# HW-DC26-Badge-20180426-1_1.net
KiCad netlist of a schematic drawn in EAGLE
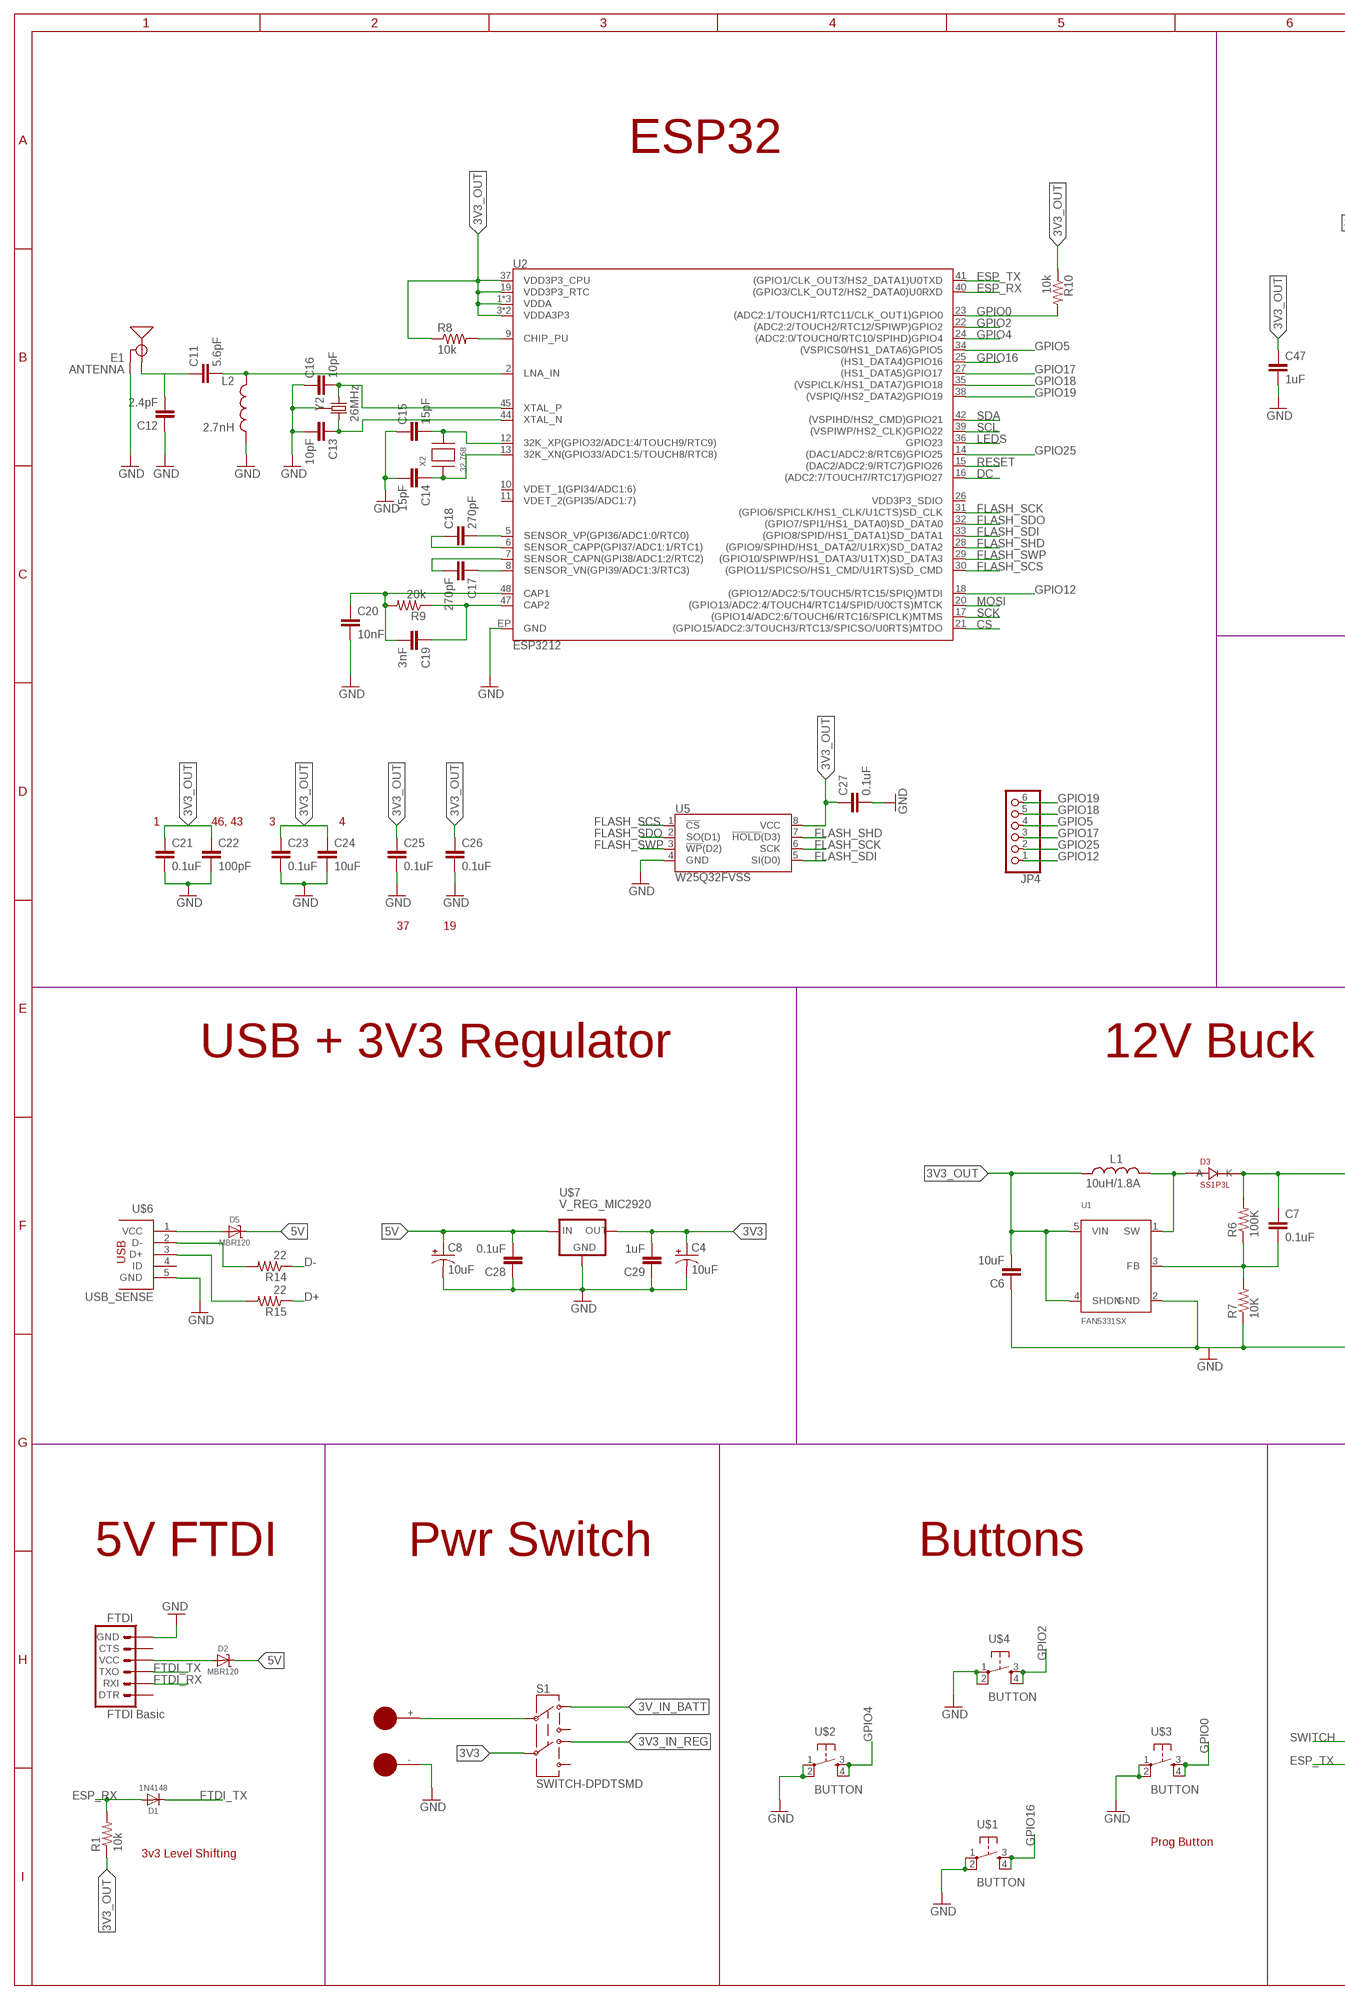
[diagram p0: schematic, sheet 1, part 1 of 2]
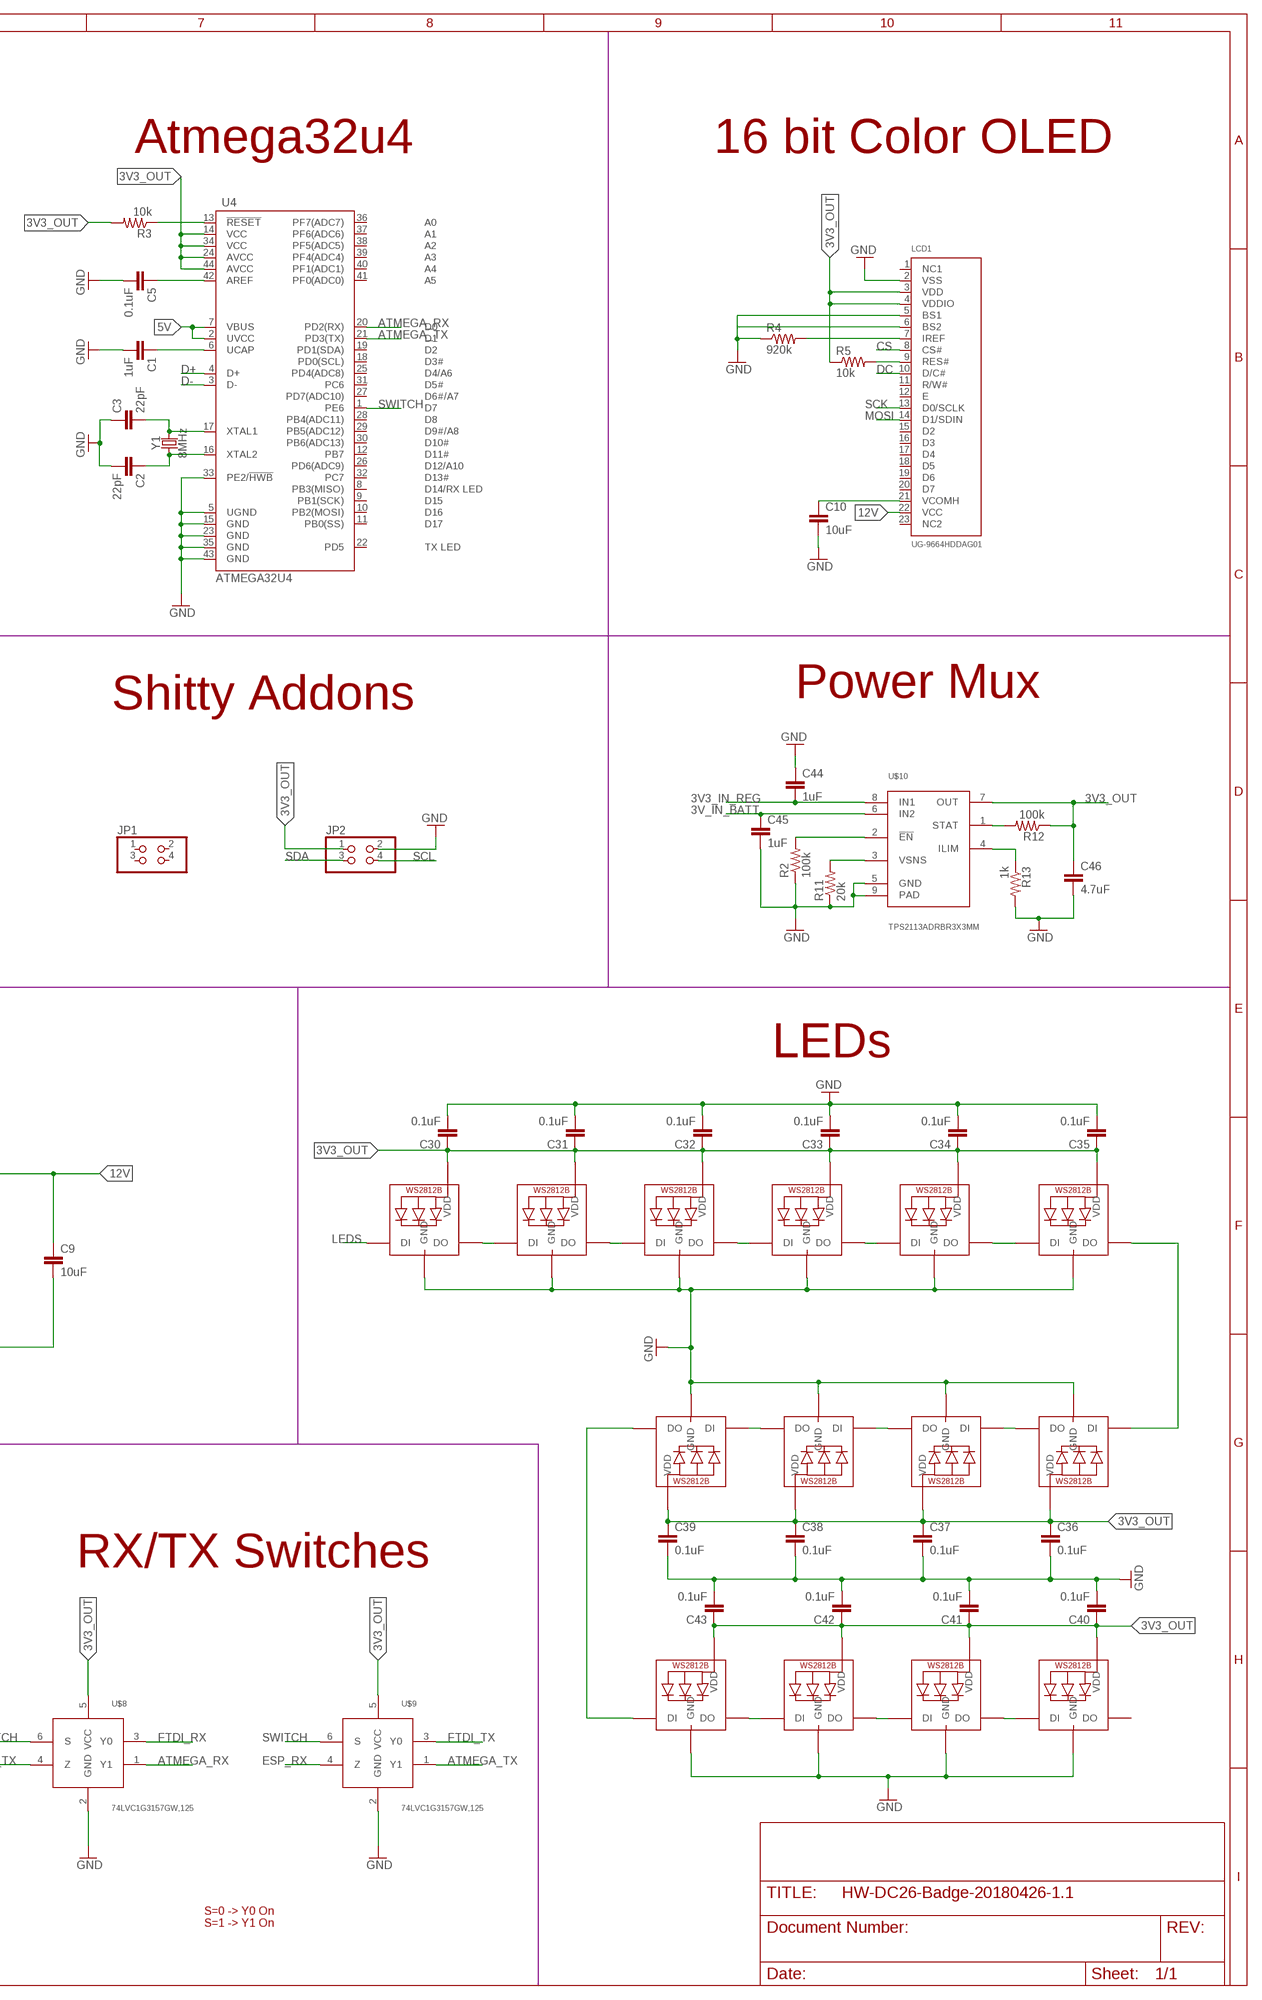
[diagram p1: schematic, sheet 1, part 2 of 2]

(export (version "E")
  (design (tool "Eeschema 10.0.6"))
  (components
    (comp (ref "C1")
      (value "1uF")
      (footprint "eagle-import:CAP0603")
      (libsource (lib "eagle-import") (part "CAP-0603-EMPTY-VALUES"))
    )
    (comp (ref "C2")
      (value "22pF")
      (footprint "eagle-import:CAP0603")
      (libsource (lib "eagle-import") (part "CAP-0603-EMPTY-VALUES"))
    )
    (comp (ref "C3")
      (value "22pF")
      (footprint "eagle-import:CAP0603")
      (libsource (lib "eagle-import") (part "CAP-0603-EMPTY-VALUES"))
    )
    (comp (ref "C4")
      (value "10uF")
      (footprint "eagle-import:EIA3216")
      (libsource (lib "eagle-import") (part "CAP_POL1206"))
    )
    (comp (ref "C5")
      (value "0.1uF")
      (footprint "eagle-import:CAP0603")
      (libsource (lib "eagle-import") (part "CAP-0603-EMPTY-VALUES"))
    )
    (comp (ref "C6")
      (value "10uF")
      (footprint "eagle-import:CAP0603")
      (fields (field (name "TOLERANCE") "10%") (field (name "VOLTAGE") "10V"))
      (libsource (lib "eagle-import") (part "CAP-0603-10UF-10V-10%"))
    )
    (comp (ref "C7")
      (value "0.1uF")
      (footprint "eagle-import:CAP0603")
      (fields (field (name "TOLERANCE") "10%") (field (name "VOLTAGE") "25V"))
      (libsource (lib "eagle-import") (part "CAP-0603-0.1UF-25V-10%"))
    )
    (comp (ref "C8")
      (value "10uF")
      (footprint "eagle-import:EIA3216")
      (libsource (lib "eagle-import") (part "CAP_POL1206"))
    )
    (comp (ref "C9")
      (value "10uF")
      (footprint "eagle-import:CAP0603")
      (fields (field (name "TOLERANCE") "20%") (field (name "VOLTAGE") "25V"))
      (libsource (lib "eagle-import") (part "CAP-0603-10UF-25V-20%"))
    )
    (comp (ref "C10")
      (value "10uF")
      (footprint "eagle-import:CAP0603")
      (libsource (lib "eagle-import") (part "CAP-0603-EMPTY-VALUES"))
    )
    (comp (ref "C11")
      (value "5.6pF")
      (footprint "eagle-import:CAP0603")
      (libsource (lib "eagle-import") (part "CAP-0603-EMPTY-VALUES"))
    )
    (comp (ref "C12")
      (value "2.4pF")
      (footprint "eagle-import:CAP0603")
      (libsource (lib "eagle-import") (part "CAP-0603-EMPTY-VALUES"))
    )
    (comp (ref "C13")
      (value "10pF")
      (footprint "eagle-import:CAP0603")
      (libsource (lib "eagle-import") (part "CAP-0603-EMPTY-VALUES"))
    )
    (comp (ref "C14")
      (value "15pF")
      (footprint "eagle-import:CAP0603")
      (libsource (lib "eagle-import") (part "CAP-0603-EMPTY-VALUES"))
    )
    (comp (ref "C15")
      (value "15pF")
      (footprint "eagle-import:CAP0603")
      (libsource (lib "eagle-import") (part "CAP-0603-EMPTY-VALUES"))
    )
    (comp (ref "C16")
      (value "10pF")
      (footprint "eagle-import:CAP0603")
      (libsource (lib "eagle-import") (part "CAP-0603-EMPTY-VALUES"))
    )
    (comp (ref "C17")
      (value "270pF")
      (footprint "eagle-import:CAP0603")
      (libsource (lib "eagle-import") (part "CAP-0603-EMPTY-VALUES"))
    )
    (comp (ref "C18")
      (value "270pF")
      (footprint "eagle-import:CAP0603")
      (libsource (lib "eagle-import") (part "CAP-0603-EMPTY-VALUES"))
    )
    (comp (ref "C19")
      (value "3nF")
      (footprint "eagle-import:CAP0603")
      (libsource (lib "eagle-import") (part "CAP-0603-EMPTY-VALUES"))
    )
    (comp (ref "C20")
      (value "10nF")
      (footprint "eagle-import:CAP0603")
      (libsource (lib "eagle-import") (part "CAP-0603-EMPTY-VALUES"))
    )
    (comp (ref "C21")
      (value "0.1uF")
      (footprint "eagle-import:CAP0603")
      (libsource (lib "eagle-import") (part "CAP-0603-EMPTY-VALUES"))
    )
    (comp (ref "C22")
      (value "100pF")
      (footprint "eagle-import:CAP0603")
      (libsource (lib "eagle-import") (part "CAP-0603-EMPTY-VALUES"))
    )
    (comp (ref "C23")
      (value "0.1uF")
      (footprint "eagle-import:CAP0603")
      (libsource (lib "eagle-import") (part "CAP-0603-EMPTY-VALUES"))
    )
    (comp (ref "C24")
      (value "10uF")
      (footprint "eagle-import:CAP0603")
      (libsource (lib "eagle-import") (part "CAP-0603-EMPTY-VALUES"))
    )
    (comp (ref "C25")
      (value "0.1uF")
      (footprint "eagle-import:CAP0603")
      (libsource (lib "eagle-import") (part "CAP-0603-EMPTY-VALUES"))
    )
    (comp (ref "C26")
      (value "0.1uF")
      (footprint "eagle-import:CAP0603")
      (libsource (lib "eagle-import") (part "CAP-0603-EMPTY-VALUES"))
    )
    (comp (ref "C27")
      (value "0.1uF")
      (footprint "eagle-import:CAP0603")
      (libsource (lib "eagle-import") (part "CAP-0603-EMPTY-VALUES"))
    )
    (comp (ref "C28")
      (value "0.1uF")
      (footprint "eagle-import:CAP0603")
      (libsource (lib "eagle-import") (part "CAP-0603-EMPTY-VALUES"))
    )
    (comp (ref "C29")
      (value "1uF")
      (footprint "eagle-import:CAP0603")
      (libsource (lib "eagle-import") (part "CAP-0603-EMPTY-VALUES"))
    )
    (comp (ref "C30")
      (value "0.1uF")
      (footprint "eagle-import:CAP0603")
      (libsource (lib "eagle-import") (part "CAP-0603-EMPTY-VALUES"))
    )
    (comp (ref "C31")
      (value "0.1uF")
      (footprint "eagle-import:CAP0603")
      (libsource (lib "eagle-import") (part "CAP-0603-EMPTY-VALUES"))
    )
    (comp (ref "C32")
      (value "0.1uF")
      (footprint "eagle-import:CAP0603")
      (libsource (lib "eagle-import") (part "CAP-0603-EMPTY-VALUES"))
    )
    (comp (ref "C33")
      (value "0.1uF")
      (footprint "eagle-import:CAP0603")
      (libsource (lib "eagle-import") (part "CAP-0603-EMPTY-VALUES"))
    )
    (comp (ref "C34")
      (value "0.1uF")
      (footprint "eagle-import:CAP0603")
      (libsource (lib "eagle-import") (part "CAP-0603-EMPTY-VALUES"))
    )
    (comp (ref "C35")
      (value "0.1uF")
      (footprint "eagle-import:CAP0603")
      (libsource (lib "eagle-import") (part "CAP-0603-EMPTY-VALUES"))
    )
    (comp (ref "C36")
      (value "0.1uF")
      (footprint "eagle-import:CAP0603")
      (libsource (lib "eagle-import") (part "CAP-0603-EMPTY-VALUES"))
    )
    (comp (ref "C37")
      (value "0.1uF")
      (footprint "eagle-import:CAP0603")
      (libsource (lib "eagle-import") (part "CAP-0603-EMPTY-VALUES"))
    )
    (comp (ref "C38")
      (value "0.1uF")
      (footprint "eagle-import:CAP0603")
      (libsource (lib "eagle-import") (part "CAP-0603-EMPTY-VALUES"))
    )
    (comp (ref "C39")
      (value "0.1uF")
      (footprint "eagle-import:CAP0603")
      (libsource (lib "eagle-import") (part "CAP-0603-EMPTY-VALUES"))
    )
    (comp (ref "C40")
      (value "0.1uF")
      (footprint "eagle-import:CAP0603")
      (libsource (lib "eagle-import") (part "CAP-0603-EMPTY-VALUES"))
    )
    (comp (ref "C41")
      (value "0.1uF")
      (footprint "eagle-import:CAP0603")
      (libsource (lib "eagle-import") (part "CAP-0603-EMPTY-VALUES"))
    )
    (comp (ref "C42")
      (value "0.1uF")
      (footprint "eagle-import:CAP0603")
      (libsource (lib "eagle-import") (part "CAP-0603-EMPTY-VALUES"))
    )
    (comp (ref "C43")
      (value "0.1uF")
      (footprint "eagle-import:CAP0603")
      (libsource (lib "eagle-import") (part "CAP-0603-EMPTY-VALUES"))
    )
    (comp (ref "C44")
      (value "1uF")
      (footprint "eagle-import:CAP0603")
      (libsource (lib "eagle-import") (part "CAP-0603-EMPTY-VALUES"))
    )
    (comp (ref "C45")
      (value "1uF")
      (footprint "eagle-import:CAP0603")
      (libsource (lib "eagle-import") (part "CAP-0603-EMPTY-VALUES"))
    )
    (comp (ref "C46")
      (value "4.7uF")
      (footprint "eagle-import:CAP0603")
      (libsource (lib "eagle-import") (part "CAP-0603-EMPTY-VALUES"))
    )
    (comp (ref "C47")
      (value "1uF")
      (footprint "eagle-import:CAP0603")
      (libsource (lib "eagle-import") (part "CAP-0603-EMPTY-VALUES"))
    )
    (comp (ref "D1")
      (value "1N4148")
      (footprint "eagle-import:SOD-323")
      (libsource (lib "eagle-import") (part "DIODESOD-323"))
    )
    (comp (ref "D2")
      (value "MBR120")
      (footprint "eagle-import:SOD-123")
      (libsource (lib "eagle-import") (part "DIODE-SCHOTTKYSOD-123"))
    )
    (comp (ref "D3")
      (value "SS1P3L")
      (footprint "eagle-import:DO220AAL")
      (libsource (lib "eagle-import") (part "SS1P3L"))
    )
    (comp (ref "D5")
      (value "MBR120")
      (footprint "eagle-import:SOD-123")
      (libsource (lib "eagle-import") (part "DIODE-SCHOTTKYSOD-123"))
    )
    (comp (ref "E1")
      (value "ANTENNA")
      (footprint "eagle-import:TRACE_ANTENNA_2.4GHZ_25.7MM_TUNED")
      (libsource (lib "eagle-import") (part "ANTENNATRACE-TUNED"))
    )
    (comp (ref "FTDI")
      (value "FTDI Basic")
      (footprint "eagle-import:1X06")
      (libsource (lib "eagle-import") (part "ARDUINO_SERIAL_PROGRAMPTH"))
    )
    (comp (ref "JP1")
      (value "PINHD-2X2")
      (footprint "eagle-import:2X02")
      (libsource (lib "eagle-import") (part "PINHD-2X2"))
    )
    (comp (ref "JP2")
      (value "PINHD-2X2")
      (footprint "eagle-import:2X02")
      (libsource (lib "eagle-import") (part "PINHD-2X2"))
    )
    (comp (ref "JP4")
      (value "PINHD-1X6")
      (footprint "eagle-import:1X06")
      (libsource (lib "eagle-import") (part "PINHD-1X6"))
    )
    (comp (ref "L1")
      (value "10uH/1.8A")
      (footprint "eagle-import:SRU5028")
      (libsource (lib "eagle-import") (part "INDUCTORSRU5028"))
    )
    (comp (ref "L2")
      (value "2.7nH")
      (footprint "eagle-import:0603")
      (libsource (lib "eagle-import") (part "SparkFun-Passives_INDUCTOR0603"))
    )
    (comp (ref "LCD1")
      (value "UG-9664HDDAG01")
      (footprint "eagle-import:UG-9664HDDAG01_WRAPAROUND")
      (libsource (lib "eagle-import") (part "DISP_OLED_UG-9664HDDAG01WRAPAROUND"))
    )
    (comp (ref "LED1")
      (value "WS2812B3535")
      (footprint "eagle-import:LED3535")
      (libsource (lib "eagle-import") (part "WS2812B3535"))
    )
    (comp (ref "LED2")
      (value "WS2812B3535")
      (footprint "eagle-import:LED3535")
      (libsource (lib "eagle-import") (part "WS2812B3535"))
    )
    (comp (ref "LED3")
      (value "WS2812B3535")
      (footprint "eagle-import:LED3535")
      (libsource (lib "eagle-import") (part "WS2812B3535"))
    )
    (comp (ref "LED4")
      (value "WS2812B3535")
      (footprint "eagle-import:LED3535")
      (libsource (lib "eagle-import") (part "WS2812B3535"))
    )
    (comp (ref "LED5")
      (value "WS2812B3535")
      (footprint "eagle-import:LED3535")
      (libsource (lib "eagle-import") (part "WS2812B3535"))
    )
    (comp (ref "LED6")
      (value "WS2812B3535")
      (footprint "eagle-import:LED3535")
      (libsource (lib "eagle-import") (part "WS2812B3535"))
    )
    (comp (ref "LED7")
      (value "WS2812B3535")
      (footprint "eagle-import:LED3535")
      (libsource (lib "eagle-import") (part "WS2812B3535"))
    )
    (comp (ref "LED8")
      (value "WS2812B3535")
      (footprint "eagle-import:LED3535")
      (libsource (lib "eagle-import") (part "WS2812B3535"))
    )
    (comp (ref "LED9")
      (value "WS2812B3535")
      (footprint "eagle-import:LED3535")
      (libsource (lib "eagle-import") (part "WS2812B3535"))
    )
    (comp (ref "LED10")
      (value "WS2812B3535")
      (footprint "eagle-import:LED3535")
      (libsource (lib "eagle-import") (part "WS2812B3535"))
    )
    (comp (ref "LED11")
      (value "WS2812B3535")
      (footprint "eagle-import:LED3535")
      (libsource (lib "eagle-import") (part "WS2812B3535"))
    )
    (comp (ref "LED12")
      (value "WS2812B3535")
      (footprint "eagle-import:LED3535")
      (libsource (lib "eagle-import") (part "WS2812B3535"))
    )
    (comp (ref "LED13")
      (value "WS2812B3535")
      (footprint "eagle-import:LED3535")
      (libsource (lib "eagle-import") (part "WS2812B3535"))
    )
    (comp (ref "LED14")
      (value "WS2812B3535")
      (footprint "eagle-import:LED3535")
      (libsource (lib "eagle-import") (part "WS2812B3535"))
    )
    (comp (ref "R1")
      (value "10k")
      (footprint "eagle-import:RES-0603")
      (libsource (lib "eagle-import") (part "RES-0603_EMPTY-FIELDS"))
    )
    (comp (ref "R2")
      (value "100k")
      (footprint "eagle-import:RES-0603")
      (libsource (lib "eagle-import") (part "RES-0603_EMPTY-FIELDS"))
    )
    (comp (ref "R3")
      (value "10k")
      (footprint "eagle-import:RES-0603")
      (libsource (lib "eagle-import") (part "RES-0603_EMPTY-FIELDS"))
    )
    (comp (ref "R4")
      (value "920k")
      (footprint "eagle-import:RES-0603")
      (libsource (lib "eagle-import") (part "RES-0603_EMPTY-FIELDS"))
    )
    (comp (ref "R5")
      (value "10k")
      (footprint "eagle-import:RES-0603")
      (libsource (lib "eagle-import") (part "RES-0603_EMPTY-FIELDS"))
    )
    (comp (ref "R6")
      (value "100K")
      (footprint "eagle-import:RES-0603")
      (fields (field (name "TOLERANCE") "5%"))
      (libsource (lib "eagle-import") (part "RES-0603-100K-5%"))
    )
    (comp (ref "R7")
      (value "10K")
      (footprint "eagle-import:RES-0603")
      (fields (field (name "TOLERANCE") "5%"))
      (libsource (lib "eagle-import") (part "RES-0603-10K-5%"))
    )
    (comp (ref "R8")
      (value "10k")
      (footprint "eagle-import:RES-0603")
      (libsource (lib "eagle-import") (part "RES-0603_EMPTY-FIELDS"))
    )
    (comp (ref "R9")
      (value "20k")
      (footprint "eagle-import:RES-0603")
      (libsource (lib "eagle-import") (part "RES-0603_EMPTY-FIELDS"))
    )
    (comp (ref "R10")
      (value "10k")
      (footprint "eagle-import:RES-0603")
      (libsource (lib "eagle-import") (part "RES-0603_EMPTY-FIELDS"))
    )
    (comp (ref "R11")
      (value "20k")
      (footprint "eagle-import:RES-0603")
      (libsource (lib "eagle-import") (part "RES-0603_EMPTY-FIELDS"))
    )
    (comp (ref "R12")
      (value "100k")
      (footprint "eagle-import:RES-0603")
      (libsource (lib "eagle-import") (part "RES-0603_EMPTY-FIELDS"))
    )
    (comp (ref "R13")
      (value "1k")
      (footprint "eagle-import:RES-0603")
      (libsource (lib "eagle-import") (part "RES-0603_EMPTY-FIELDS"))
    )
    (comp (ref "R14")
      (value "22")
      (footprint "eagle-import:RES-0603")
      (libsource (lib "eagle-import") (part "RES-0603_EMPTY-FIELDS"))
    )
    (comp (ref "R15")
      (value "22")
      (footprint "eagle-import:RES-0603")
      (libsource (lib "eagle-import") (part "RES-0603_EMPTY-FIELDS"))
    )
    (comp (ref "S1")
      (value "SWITCH-DPDTSMD")
      (footprint "eagle-import:AYZ0202")
      (libsource (lib "eagle-import") (part "SWITCH-DPDTSMD"))
    )
    (comp (ref "U$1")
      (value "BUTTON")
      (footprint "eagle-import:BUTTON")
      (libsource (lib "eagle-import") (part "BUTTON"))
    )
    (comp (ref "U$2")
      (value "BUTTON")
      (footprint "eagle-import:BUTTON")
      (libsource (lib "eagle-import") (part "BUTTON"))
    )
    (comp (ref "U$3")
      (value "BUTTON")
      (footprint "eagle-import:BUTTON")
      (libsource (lib "eagle-import") (part "BUTTON"))
    )
    (comp (ref "U$4")
      (value "BUTTON")
      (footprint "eagle-import:BUTTON")
      (libsource (lib "eagle-import") (part "BUTTON"))
    )
    (comp (ref "U$5")
      (value "BAT_HOLD")
      (footprint "eagle-import:AA")
      (libsource (lib "eagle-import") (part "BAT_HOLD"))
    )
    (comp (ref "U$6")
      (value "USB_SENSE")
      (footprint "eagle-import:USB-MICRO-TH-SUPPORT")
      (libsource (lib "eagle-import") (part "USB_SENSE"))
    )
    (comp (ref "U$7")
      (value "V_REG_MIC2920")
      (footprint "eagle-import:SOT223")
      (libsource (lib "eagle-import") (part "V_REG_MIC2920"))
    )
    (comp (ref "U$8")
      (value "74LVC1G3157GW,125")
      (footprint "eagle-import:SOT-363")
      (libsource (lib "eagle-import") (part "74LVC1G3157GW,125"))
    )
    (comp (ref "U$9")
      (value "74LVC1G3157GW,125")
      (footprint "eagle-import:SOT-363")
      (libsource (lib "eagle-import") (part "74LVC1G3157GW,125"))
    )
    (comp (ref "U$10")
      (value "TPS2113ADRBR3X3MM")
      (footprint "eagle-import:8-VDFN")
      (libsource (lib "eagle-import") (part "TPS2113ADRBR3X3MM"))
    )
    (comp (ref "U1")
      (value "FAN5331SX")
      (footprint "eagle-import:SOT23-5")
      (libsource (lib "eagle-import") (part "FAN5331"))
    )
    (comp (ref "U2")
      (value "ESP3212")
      (footprint "eagle-import:QFN48-0.4MM")
      (libsource (lib "eagle-import") (part "ESP3212"))
    )
    (comp (ref "U4")
      (value "ATMEGA32U4")
      (footprint "eagle-import:QFN-44-NOPAD_1_1-OUTFAKES")
      (libsource (lib "eagle-import") (part "ATMEGA32U4OUTFAKES"))
    )
    (comp (ref "U5")
      (value "W25Q32FVSS")
      (footprint "eagle-import:SOIC-8")
      (libsource (lib "eagle-import") (part "W25Q32FVSS"))
    )
    (comp (ref "X2")
      (value "32.768")
      (footprint "eagle-import:XTAL3215")
      (libsource (lib "eagle-import") (part "XTAL-3.2X1.5"))
    )
    (comp (ref "Y1")
      (value "8MHz")
      (footprint "eagle-import:CRYSTAL-SMD-5X3.2-4PAD")
      (libsource (lib "eagle-import") (part "CRYSTAL-8MHZSMD-5X3.2"))
    )
    (comp (ref "Y2")
      (value "26MHz")
      (footprint "eagle-import:CRYSTAL-SMD-3.2X2.5")
      (libsource (lib "eagle-import") (part "CRYSTAL-GROUNDED3.2X2.5"))
    )
  )
  (nets
    (net (code "1") (name "/ATMEGA_RX") (class "Default")
      (node (ref "U$8") (pin "1") (pinfunction "Y1_1") (pintype "bidirectional"))
      (node (ref "U4") (pin "20") (pinfunction "PD2(RX)_20") (pintype "bidirectional"))
    )
    (net (code "2") (name "/ATMEGA_TX") (class "Default")
      (node (ref "U$9") (pin "1") (pinfunction "Y1_1") (pintype "bidirectional"))
      (node (ref "U4") (pin "21") (pinfunction "PD3(TX)_21") (pintype "bidirectional"))
    )
    (net (code "3") (name "/CS") (class "Default")
      (node (ref "LCD1") (pin "8") (pinfunction "CS#_8") (pintype "bidirectional"))
      (node (ref "U2") (pin "21") (pinfunction "(GPIO15/ADC2:3/TOUCH3/RTC13/SPICSO/U0RTS)MTDO_21") (pintype "bidirectional"))
    )
    (net (code "4") (name "/D+") (class "Default")
      (node (ref "R15") (pin "1") (pinfunction "1_1") (pintype "passive"))
      (node (ref "U4") (pin "4") (pinfunction "D+_4") (pintype "bidirectional"))
    )
    (net (code "5") (name "/D-") (class "Default")
      (node (ref "R14") (pin "1") (pinfunction "1_1") (pintype "passive"))
      (node (ref "U4") (pin "3") (pinfunction "D-_3") (pintype "bidirectional"))
    )
    (net (code "6") (name "/DC") (class "Default")
      (node (ref "LCD1") (pin "10") (pinfunction "D/C#_10") (pintype "bidirectional"))
      (node (ref "U2") (pin "16") (pinfunction "(ADC2:7/TOUCH7/RTC17)GPIO27_16") (pintype "bidirectional"))
    )
    (net (code "7") (name "/ESP_RX") (class "Default")
      (node (ref "D1") (pin "A") (pinfunction "A_A") (pintype "passive"))
      (node (ref "R1") (pin "2") (pinfunction "2_2") (pintype "passive"))
      (node (ref "U$9") (pin "4") (pinfunction "Z_4") (pintype "bidirectional"))
      (node (ref "U2") (pin "40") (pinfunction "(GPIO3/CLK_OUT2/HS2_DATA0)U0RXD_40") (pintype "bidirectional"))
    )
    (net (code "8") (name "/ESP_TX") (class "Default")
      (node (ref "U$8") (pin "4") (pinfunction "Z_4") (pintype "bidirectional"))
      (node (ref "U2") (pin "41") (pinfunction "(GPIO1/CLK_OUT3/HS2_DATA1)U0TXD_41") (pintype "bidirectional"))
    )
    (net (code "9") (name "/FLASH_SCK") (class "Default")
      (node (ref "U2") (pin "31") (pinfunction "(GPIO6/SPICLK/HS1_CLK/U1CTS)SD_CLK_31") (pintype "bidirectional"))
      (node (ref "U5") (pin "6") (pinfunction "SCK_6") (pintype "bidirectional"))
    )
    (net (code "10") (name "/FLASH_SCS") (class "Default")
      (node (ref "U2") (pin "30") (pinfunction "(GPIO11/SPICSO/HS1_CMD/U1RTS)SD_CMD_30") (pintype "bidirectional"))
      (node (ref "U5") (pin "1") (pinfunction "~{CS}_1") (pintype "bidirectional"))
    )
    (net (code "11") (name "/FLASH_SDI") (class "Default")
      (node (ref "U2") (pin "33") (pinfunction "(GPIO8/SPID/HS1_DATA1)SD_DATA1_33") (pintype "bidirectional"))
      (node (ref "U5") (pin "5") (pinfunction "SI(D0)_5") (pintype "bidirectional"))
    )
    (net (code "12") (name "/FLASH_SDO") (class "Default")
      (node (ref "U2") (pin "32") (pinfunction "(GPIO7/SPI1/HS1_DATA0)SD_DATA0_32") (pintype "bidirectional"))
      (node (ref "U5") (pin "2") (pinfunction "SO(D1)_2") (pintype "bidirectional"))
    )
    (net (code "13") (name "/FLASH_SHD") (class "Default")
      (node (ref "U2") (pin "28") (pinfunction "(GPIO9/SPIHD/HS1_DATA2/U1RX)SD_DATA2_28") (pintype "bidirectional"))
      (node (ref "U5") (pin "7") (pinfunction "~{HOLD}(D3)_7") (pintype "bidirectional"))
    )
    (net (code "14") (name "/FLASH_SWP") (class "Default")
      (node (ref "U2") (pin "29") (pinfunction "(GPIO10/SPIWP/HS1_DATA3/U1TX)SD_DATA3_29") (pintype "bidirectional"))
      (node (ref "U5") (pin "3") (pinfunction "~{WP}(D2)_3") (pintype "bidirectional"))
    )
    (net (code "15") (name "/FTDI_RX") (class "Default")
      (node (ref "FTDI") (pin "2") (pinfunction "RXI_2") (pintype "passive"))
      (node (ref "U$8") (pin "3") (pinfunction "Y0_3") (pintype "bidirectional"))
    )
    (net (code "16") (name "/FTDI_TX") (class "Default")
      (node (ref "D1") (pin "C") (pinfunction "C_C") (pintype "passive"))
      (node (ref "FTDI") (pin "3") (pinfunction "TXO_3") (pintype "passive"))
      (node (ref "U$9") (pin "3") (pinfunction "Y0_3") (pintype "bidirectional"))
    )
    (net (code "17") (name "/GPIO0") (class "Default")
      (node (ref "R10") (pin "2") (pinfunction "2_2") (pintype "passive"))
      (node (ref "U$3") (pin "3") (pinfunction "3_3") (pintype "passive"))
      (node (ref "U$3") (pin "4") (pinfunction "4_4") (pintype "passive"))
      (node (ref "U2") (pin "23") (pinfunction "(ADC2:1/TOUCH1/RTC11/CLK_OUT1)GPIO0_23") (pintype "bidirectional"))
    )
    (net (code "18") (name "/GPIO2") (class "Default")
      (node (ref "U$4") (pin "3") (pinfunction "3_3") (pintype "passive"))
      (node (ref "U$4") (pin "4") (pinfunction "4_4") (pintype "passive"))
      (node (ref "U2") (pin "22") (pinfunction "(ADC2:2/TOUCH2/RTC12/SPIWP)GPIO2_22") (pintype "bidirectional"))
    )
    (net (code "19") (name "/GPIO4") (class "Default")
      (node (ref "U$2") (pin "3") (pinfunction "3_3") (pintype "passive"))
      (node (ref "U$2") (pin "4") (pinfunction "4_4") (pintype "passive"))
      (node (ref "U2") (pin "24") (pinfunction "(ADC2:0/TOUCH0/RTC10/SPIHD)GPIO4_24") (pintype "bidirectional"))
    )
    (net (code "20") (name "/GPIO5") (class "Default")
      (node (ref "JP4") (pin "4") (pinfunction "4_4") (pintype "passive"))
      (node (ref "U2") (pin "34") (pinfunction "(VSPICS0/HS1_DATA6)GPIO5_34") (pintype "bidirectional"))
    )
    (net (code "21") (name "/GPIO12") (class "Default")
      (node (ref "JP4") (pin "1") (pinfunction "1_1") (pintype "passive"))
      (node (ref "U2") (pin "18") (pinfunction "(GPIO12/ADC2:5/TOUCH5/RTC15/SPIQ)MTDI_18") (pintype "bidirectional"))
    )
    (net (code "22") (name "/GPIO16") (class "Default")
      (node (ref "U$1") (pin "3") (pinfunction "3_3") (pintype "passive"))
      (node (ref "U$1") (pin "4") (pinfunction "4_4") (pintype "passive"))
      (node (ref "U2") (pin "25") (pinfunction "(HS1_DATA4)GPIO16_25") (pintype "bidirectional"))
    )
    (net (code "23") (name "/GPIO17") (class "Default")
      (node (ref "JP4") (pin "3") (pinfunction "3_3") (pintype "passive"))
      (node (ref "U2") (pin "27") (pinfunction "(HS1_DATA5)GPIO17_27") (pintype "bidirectional"))
    )
    (net (code "24") (name "/GPIO18") (class "Default")
      (node (ref "JP4") (pin "5") (pinfunction "5_5") (pintype "passive"))
      (node (ref "U2") (pin "35") (pinfunction "(VSPICLK/HS1_DATA7)GPIO18_35") (pintype "bidirectional"))
    )
    (net (code "25") (name "/GPIO19") (class "Default")
      (node (ref "JP4") (pin "6") (pinfunction "6_6") (pintype "passive"))
      (node (ref "U2") (pin "38") (pinfunction "(VSPIQ/HS2_DATA2)GPIO19_38") (pintype "bidirectional"))
    )
    (net (code "26") (name "/GPIO25") (class "Default")
      (node (ref "JP4") (pin "2") (pinfunction "2_2") (pintype "passive"))
      (node (ref "U2") (pin "14") (pinfunction "(DAC1/ADC2:8/RTC6)GPIO25_14") (pintype "bidirectional"))
    )
    (net (code "27") (name "/LEDS") (class "Default")
      (node (ref "LED5") (pin "1") (pinfunction "DI_1") (pintype "input"))
      (node (ref "U2") (pin "36") (pinfunction "GPIO23_36") (pintype "bidirectional"))
    )
    (net (code "28") (name "/MOSI") (class "Default")
      (node (ref "LCD1") (pin "14") (pinfunction "D1/SDIN_14") (pintype "bidirectional"))
      (node (ref "U2") (pin "20") (pinfunction "(GPIO13/ADC2:4/TOUCH4/RTC14/SPID/U0CTS)MTCK_20") (pintype "bidirectional"))
    )
    (net (code "29") (name "/RESET") (class "Default")
      (node (ref "LCD1") (pin "9") (pinfunction "RES#_9") (pintype "bidirectional"))
      (node (ref "R5") (pin "2") (pinfunction "2_2") (pintype "passive"))
      (node (ref "U2") (pin "15") (pinfunction "(DAC2/ADC2:9/RTC7)GPIO26_15") (pintype "bidirectional"))
    )
    (net (code "30") (name "/SCK") (class "Default")
      (node (ref "LCD1") (pin "13") (pinfunction "D0/SCLK_13") (pintype "bidirectional"))
      (node (ref "U2") (pin "17") (pinfunction "(GPIO14/ADC2:6/TOUCH6/RTC16/SPICLK)MTMS_17") (pintype "bidirectional"))
    )
    (net (code "31") (name "/SCL") (class "Default")
      (node (ref "JP2") (pin "4") (pinfunction "4_4") (pintype "passive"))
      (node (ref "U2") (pin "39") (pinfunction "(VSPIWP/HS2_CLK)GPIO22_39") (pintype "bidirectional"))
    )
    (net (code "32") (name "/SDA") (class "Default")
      (node (ref "JP2") (pin "3") (pinfunction "3_3") (pintype "passive"))
      (node (ref "U2") (pin "42") (pinfunction "(VSPIHD/HS2_CMD)GPIO21_42") (pintype "bidirectional"))
    )
    (net (code "33") (name "/SWITCH") (class "Default")
      (node (ref "U$8") (pin "6") (pinfunction "S_6") (pintype "bidirectional"))
      (node (ref "U$9") (pin "6") (pinfunction "S_6") (pintype "bidirectional"))
      (node (ref "U4") (pin "1") (pinfunction "PE6_1") (pintype "bidirectional"))
    )
    (net (code "34") (name "3V3") (class "Default")
      (node (ref "C29") (pin "2") (pinfunction "2_2") (pintype "passive"))
      (node (ref "C4") (pin "A") (pinfunction "+_A") (pintype "passive"))
      (node (ref "S1") (pin "5") (pinfunction "5_5") (pintype "bidirectional"))
      (node (ref "U$7") (pin "3") (pinfunction "OUT_3") (pintype "output"))
    )
    (net (code "35") (name "3V3_IN_REG") (class "Default")
      (node (ref "C44") (pin "2") (pinfunction "2_2") (pintype "passive"))
      (node (ref "S1") (pin "4") (pinfunction "4_4") (pintype "bidirectional"))
      (node (ref "U$10") (pin "8") (pinfunction "IN1_8") (pintype "bidirectional"))
    )
    (net (code "36") (name "3V3_OUT") (class "Default")
      (node (ref "C21") (pin "1") (pinfunction "1_1") (pintype "passive"))
      (node (ref "C22") (pin "1") (pinfunction "1_1") (pintype "passive"))
      (node (ref "C23") (pin "1") (pinfunction "1_1") (pintype "passive"))
      (node (ref "C24") (pin "1") (pinfunction "1_1") (pintype "passive"))
      (node (ref "C25") (pin "1") (pinfunction "1_1") (pintype "passive"))
      (node (ref "C26") (pin "1") (pinfunction "1_1") (pintype "passive"))
      (node (ref "C27") (pin "1") (pinfunction "1_1") (pintype "passive"))
      (node (ref "C30") (pin "1") (pinfunction "1_1") (pintype "passive"))
      (node (ref "C31") (pin "1") (pinfunction "1_1") (pintype "passive"))
      (node (ref "C32") (pin "1") (pinfunction "1_1") (pintype "passive"))
      (node (ref "C33") (pin "1") (pinfunction "1_1") (pintype "passive"))
      (node (ref "C34") (pin "1") (pinfunction "1_1") (pintype "passive"))
      (node (ref "C35") (pin "1") (pinfunction "1_1") (pintype "passive"))
      (node (ref "C36") (pin "1") (pinfunction "1_1") (pintype "passive"))
      (node (ref "C37") (pin "1") (pinfunction "1_1") (pintype "passive"))
      (node (ref "C38") (pin "1") (pinfunction "1_1") (pintype "passive"))
      (node (ref "C39") (pin "1") (pinfunction "1_1") (pintype "passive"))
      (node (ref "C40") (pin "1") (pinfunction "1_1") (pintype "passive"))
      (node (ref "C41") (pin "1") (pinfunction "1_1") (pintype "passive"))
      (node (ref "C42") (pin "1") (pinfunction "1_1") (pintype "passive"))
      (node (ref "C43") (pin "1") (pinfunction "1_1") (pintype "passive"))
      (node (ref "C46") (pin "1") (pinfunction "1_1") (pintype "passive"))
      (node (ref "C47") (pin "1") (pinfunction "1_1") (pintype "passive"))
      (node (ref "C6") (pin "2") (pinfunction "2_2") (pintype "passive"))
      (node (ref "JP2") (pin "1") (pinfunction "1_1") (pintype "passive"))
      (node (ref "L1") (pin "1") (pinfunction "1_1") (pintype "passive"))
      (node (ref "LCD1") (pin "3") (pinfunction "VDD_3") (pintype "bidirectional"))
      (node (ref "LCD1") (pin "4") (pinfunction "VDDIO_4") (pintype "bidirectional"))
      (node (ref "LED1") (pin "2") (pinfunction "VDD_2") (pintype "power_in"))
      (node (ref "LED10") (pin "2") (pinfunction "VDD_2") (pintype "power_in"))
      (node (ref "LED11") (pin "2") (pinfunction "VDD_2") (pintype "power_in"))
      (node (ref "LED12") (pin "2") (pinfunction "VDD_2") (pintype "power_in"))
      (node (ref "LED13") (pin "2") (pinfunction "VDD_2") (pintype "power_in"))
      (node (ref "LED14") (pin "2") (pinfunction "VDD_2") (pintype "power_in"))
      (node (ref "LED2") (pin "2") (pinfunction "VDD_2") (pintype "power_in"))
      (node (ref "LED3") (pin "2") (pinfunction "VDD_2") (pintype "power_in"))
      (node (ref "LED4") (pin "2") (pinfunction "VDD_2") (pintype "power_in"))
      (node (ref "LED5") (pin "2") (pinfunction "VDD_2") (pintype "power_in"))
      (node (ref "LED6") (pin "2") (pinfunction "VDD_2") (pintype "power_in"))
      (node (ref "LED7") (pin "2") (pinfunction "VDD_2") (pintype "power_in"))
      (node (ref "LED8") (pin "2") (pinfunction "VDD_2") (pintype "power_in"))
      (node (ref "LED9") (pin "2") (pinfunction "VDD_2") (pintype "power_in"))
      (node (ref "R1") (pin "1") (pinfunction "1_1") (pintype "passive"))
      (node (ref "R10") (pin "1") (pinfunction "1_1") (pintype "passive"))
      (node (ref "R12") (pin "1") (pinfunction "1_1") (pintype "passive"))
      (node (ref "R3") (pin "2") (pinfunction "2_2") (pintype "passive"))
      (node (ref "R5") (pin "1") (pinfunction "1_1") (pintype "passive"))
      (node (ref "R8") (pin "1") (pinfunction "1_1") (pintype "passive"))
      (node (ref "U$10") (pin "7") (pinfunction "OUT_7") (pintype "bidirectional"))
      (node (ref "U$8") (pin "5") (pinfunction "VCC_5") (pintype "bidirectional"))
      (node (ref "U$9") (pin "5") (pinfunction "VCC_5") (pintype "bidirectional"))
      (node (ref "U1") (pin "4") (pinfunction "SHDN_4") (pintype "bidirectional"))
      (node (ref "U1") (pin "5") (pinfunction "VIN_5") (pintype "bidirectional"))
      (node (ref "U2") (pin "1") (pinfunction "VDDA_1") (pintype "bidirectional"))
      (node (ref "U2") (pin "19") (pinfunction "VDD3P3_RTC_19") (pintype "bidirectional"))
      (node (ref "U2") (pin "3") (pinfunction "VDDA3P3_3") (pintype "bidirectional"))
      (node (ref "U2") (pin "37") (pinfunction "VDD3P3_CPU_37") (pintype "bidirectional"))
      (node (ref "U2") (pin "4") (pinfunction "VDDA3P3_4") (pintype "bidirectional"))
      (node (ref "U2") (pin "43") (pinfunction "VDDA_43") (pintype "bidirectional"))
      (node (ref "U2") (pin "46") (pinfunction "VDDA_46") (pintype "bidirectional"))
      (node (ref "U4") (pin "14") (pinfunction "VCC_14") (pintype "bidirectional"))
      (node (ref "U4") (pin "24") (pinfunction "AVCC_24") (pintype "bidirectional"))
      (node (ref "U4") (pin "34") (pinfunction "VCC_34") (pintype "bidirectional"))
      (node (ref "U4") (pin "44") (pinfunction "AVCC_44") (pintype "bidirectional"))
      (node (ref "U5") (pin "8") (pinfunction "VCC_8") (pintype "bidirectional"))
    )
    (net (code "37") (name "3V_IN_BATT") (class "Default")
      (node (ref "C45") (pin "1") (pinfunction "1_1") (pintype "passive"))
      (node (ref "S1") (pin "1") (pinfunction "1_1") (pintype "bidirectional"))
      (node (ref "U$10") (pin "6") (pinfunction "IN2_6") (pintype "bidirectional"))
    )
    (net (code "38") (name "5V") (class "Default")
      (node (ref "C28") (pin "2") (pinfunction "2_2") (pintype "passive"))
      (node (ref "C8") (pin "A") (pinfunction "+_A") (pintype "passive"))
      (node (ref "D2") (pin "C") (pinfunction "C_C") (pintype "passive"))
      (node (ref "D5") (pin "C") (pinfunction "C_C") (pintype "passive"))
      (node (ref "U$7") (pin "1") (pinfunction "IN_1") (pintype "input"))
      (node (ref "U4") (pin "2") (pinfunction "UVCC_2") (pintype "bidirectional"))
      (node (ref "U4") (pin "7") (pinfunction "VBUS_7") (pintype "bidirectional"))
    )
    (net (code "39") (name "12V") (class "Default")
      (node (ref "C7") (pin "1") (pinfunction "1_1") (pintype "passive"))
      (node (ref "C9") (pin "1") (pinfunction "1_1") (pintype "passive"))
      (node (ref "D3") (pin "P$1") (pinfunction "K_P$1") (pintype "bidirectional"))
      (node (ref "LCD1") (pin "22") (pinfunction "VCC_22") (pintype "bidirectional"))
      (node (ref "R6") (pin "2") (pinfunction "2_2") (pintype "passive"))
    )
    (net (code "40") (name "GND") (class "Default")
      (node (ref "C1") (pin "2") (pinfunction "2_2") (pintype "passive"))
      (node (ref "C10") (pin "2") (pinfunction "2_2") (pintype "passive"))
      (node (ref "C12") (pin "1") (pinfunction "1_1") (pintype "passive"))
      (node (ref "C13") (pin "2") (pinfunction "2_2") (pintype "passive"))
      (node (ref "C14") (pin "2") (pinfunction "2_2") (pintype "passive"))
      (node (ref "C15") (pin "1") (pinfunction "1_1") (pintype "passive"))
      (node (ref "C16") (pin "1") (pinfunction "1_1") (pintype "passive"))
      (node (ref "C2") (pin "2") (pinfunction "2_2") (pintype "passive"))
      (node (ref "C20") (pin "2") (pinfunction "2_2") (pintype "passive"))
      (node (ref "C21") (pin "2") (pinfunction "2_2") (pintype "passive"))
      (node (ref "C22") (pin "2") (pinfunction "2_2") (pintype "passive"))
      (node (ref "C23") (pin "2") (pinfunction "2_2") (pintype "passive"))
      (node (ref "C24") (pin "2") (pinfunction "2_2") (pintype "passive"))
      (node (ref "C25") (pin "2") (pinfunction "2_2") (pintype "passive"))
      (node (ref "C26") (pin "2") (pinfunction "2_2") (pintype "passive"))
      (node (ref "C27") (pin "2") (pinfunction "2_2") (pintype "passive"))
      (node (ref "C28") (pin "1") (pinfunction "1_1") (pintype "passive"))
      (node (ref "C29") (pin "1") (pinfunction "1_1") (pintype "passive"))
      (node (ref "C3") (pin "1") (pinfunction "1_1") (pintype "passive"))
      (node (ref "C30") (pin "2") (pinfunction "2_2") (pintype "passive"))
      (node (ref "C31") (pin "2") (pinfunction "2_2") (pintype "passive"))
      (node (ref "C32") (pin "2") (pinfunction "2_2") (pintype "passive"))
      (node (ref "C33") (pin "2") (pinfunction "2_2") (pintype "passive"))
      (node (ref "C34") (pin "2") (pinfunction "2_2") (pintype "passive"))
      (node (ref "C35") (pin "2") (pinfunction "2_2") (pintype "passive"))
      (node (ref "C36") (pin "2") (pinfunction "2_2") (pintype "passive"))
      (node (ref "C37") (pin "2") (pinfunction "2_2") (pintype "passive"))
      (node (ref "C38") (pin "2") (pinfunction "2_2") (pintype "passive"))
      (node (ref "C39") (pin "2") (pinfunction "2_2") (pintype "passive"))
      (node (ref "C4") (pin "C") (pinfunction "-_C") (pintype "passive"))
      (node (ref "C40") (pin "2") (pinfunction "2_2") (pintype "passive"))
      (node (ref "C41") (pin "2") (pinfunction "2_2") (pintype "passive"))
      (node (ref "C42") (pin "2") (pinfunction "2_2") (pintype "passive"))
      (node (ref "C43") (pin "2") (pinfunction "2_2") (pintype "passive"))
      (node (ref "C44") (pin "1") (pinfunction "1_1") (pintype "passive"))
      (node (ref "C45") (pin "2") (pinfunction "2_2") (pintype "passive"))
      (node (ref "C46") (pin "2") (pinfunction "2_2") (pintype "passive"))
      (node (ref "C47") (pin "2") (pinfunction "2_2") (pintype "passive"))
      (node (ref "C5") (pin "2") (pinfunction "2_2") (pintype "passive"))
      (node (ref "C6") (pin "1") (pinfunction "1_1") (pintype "passive"))
      (node (ref "C8") (pin "C") (pinfunction "-_C") (pintype "passive"))
      (node (ref "C9") (pin "2") (pinfunction "2_2") (pintype "passive"))
      (node (ref "E1") (pin "GND") (pinfunction "GND_GND") (pintype "bidirectional"))
      (node (ref "E1") (pin "GND2") (pinfunction "GND_GND2") (pintype "bidirectional"))
      (node (ref "FTDI") (pin "6") (pinfunction "GND_6") (pintype "passive"))
      (node (ref "JP2") (pin "2") (pinfunction "2_2") (pintype "passive"))
      (node (ref "L2") (pin "2") (pinfunction "2_2") (pintype "passive"))
      (node (ref "LCD1") (pin "2") (pinfunction "VSS_2") (pintype "bidirectional"))
      (node (ref "LCD1") (pin "5") (pinfunction "BS1_5") (pintype "bidirectional"))
      (node (ref "LED1") (pin "4") (pinfunction "GND_4") (pintype "power_in"))
      (node (ref "LED10") (pin "4") (pinfunction "GND_4") (pintype "power_in"))
      (node (ref "LED11") (pin "4") (pinfunction "GND_4") (pintype "power_in"))
      (node (ref "LED12") (pin "4") (pinfunction "GND_4") (pintype "power_in"))
      (node (ref "LED13") (pin "4") (pinfunction "GND_4") (pintype "power_in"))
      (node (ref "LED14") (pin "4") (pinfunction "GND_4") (pintype "power_in"))
      (node (ref "LED2") (pin "4") (pinfunction "GND_4") (pintype "power_in"))
      (node (ref "LED3") (pin "4") (pinfunction "GND_4") (pintype "power_in"))
      (node (ref "LED4") (pin "4") (pinfunction "GND_4") (pintype "power_in"))
      (node (ref "LED5") (pin "4") (pinfunction "GND_4") (pintype "power_in"))
      (node (ref "LED6") (pin "4") (pinfunction "GND_4") (pintype "power_in"))
      (node (ref "LED7") (pin "4") (pinfunction "GND_4") (pintype "power_in"))
      (node (ref "LED8") (pin "4") (pinfunction "GND_4") (pintype "power_in"))
      (node (ref "LED9") (pin "4") (pinfunction "GND_4") (pintype "power_in"))
      (node (ref "R11") (pin "1") (pinfunction "1_1") (pintype "passive"))
      (node (ref "R13") (pin "2") (pinfunction "2_2") (pintype "passive"))
      (node (ref "R2") (pin "1") (pinfunction "1_1") (pintype "passive"))
      (node (ref "R4") (pin "1") (pinfunction "1_1") (pintype "passive"))
      (node (ref "R7") (pin "1") (pinfunction "1_1") (pintype "passive"))
      (node (ref "U$1") (pin "1") (pinfunction "1_1") (pintype "passive"))
      (node (ref "U$1") (pin "2") (pinfunction "2_2") (pintype "passive"))
      (node (ref "U$10") (pin "5") (pinfunction "GND_5") (pintype "bidirectional"))
      (node (ref "U$10") (pin "9") (pinfunction "PAD_9") (pintype "bidirectional"))
      (node (ref "U$2") (pin "1") (pinfunction "1_1") (pintype "passive"))
      (node (ref "U$2") (pin "2") (pinfunction "2_2") (pintype "passive"))
      (node (ref "U$3") (pin "1") (pinfunction "1_1") (pintype "passive"))
      (node (ref "U$3") (pin "2") (pinfunction "2_2") (pintype "passive"))
      (node (ref "U$4") (pin "1") (pinfunction "1_1") (pintype "passive"))
      (node (ref "U$4") (pin "2") (pinfunction "2_2") (pintype "passive"))
      (node (ref "U$5") (pin "-") (pinfunction "-_-") (pintype "bidirectional"))
      (node (ref "U$6") (pin "5") (pinfunction "GND_5") (pintype "bidirectional"))
      (node (ref "U$7") (pin "2") (pinfunction "GND_2") (pintype "input"))
      (node (ref "U$7") (pin "4") (pinfunction "GND_4") (pintype "input"))
      (node (ref "U$8") (pin "2") (pinfunction "GND_2") (pintype "bidirectional"))
      (node (ref "U$9") (pin "2") (pinfunction "GND_2") (pintype "bidirectional"))
      (node (ref "U1") (pin "2") (pinfunction "GND_2") (pintype "bidirectional"))
      (node (ref "U2") (pin "EP") (pinfunction "GND_EP") (pintype "bidirectional"))
      (node (ref "U4") (pin "15") (pinfunction "GND_15") (pintype "bidirectional"))
      (node (ref "U4") (pin "23") (pinfunction "GND_23") (pintype "bidirectional"))
      (node (ref "U4") (pin "33") (pinfunction "PE2/~{HWB}_33") (pintype "bidirectional"))
      (node (ref "U4") (pin "35") (pinfunction "GND_35") (pintype "bidirectional"))
      (node (ref "U4") (pin "43") (pinfunction "GND_43") (pintype "bidirectional"))
      (node (ref "U4") (pin "5") (pinfunction "UGND_5") (pintype "bidirectional"))
      (node (ref "U5") (pin "4") (pinfunction "GND_4") (pintype "bidirectional"))
      (node (ref "Y2") (pin "2") (pinfunction "GND_2") (pintype "passive"))
      (node (ref "Y2") (pin "4") (pinfunction "GND_4") (pintype "passive"))
    )
    (net (code "41") (name "Net-(D3-A)") (class "Default")
      (node (ref "D3") (pin "P$2") (pinfunction "A_P$2") (pintype "bidirectional"))
      (node (ref "L1") (pin "2") (pinfunction "2_2") (pintype "passive"))
      (node (ref "U1") (pin "1") (pinfunction "SW_1") (pintype "bidirectional"))
    )
    (net (code "42") (name "Net-(E1-SIGNAL)") (class "Default")
      (node (ref "C11") (pin "1") (pinfunction "1_1") (pintype "passive"))
      (node (ref "C12") (pin "2") (pinfunction "2_2") (pintype "passive"))
      (node (ref "E1") (pin "ANT") (pinfunction "SIGNAL_ANT") (pintype "bidirectional"))
    )
    (net (code "43") (name "Net-(FTDI-VCC)") (class "Default")
      (node (ref "D2") (pin "A") (pinfunction "A_A") (pintype "passive"))
      (node (ref "FTDI") (pin "4") (pinfunction "VCC_4") (pintype "passive"))
    )
    (net (code "44") (name "Net-(LCD1-IREF)") (class "Default")
      (node (ref "LCD1") (pin "7") (pinfunction "IREF_7") (pintype "bidirectional"))
      (node (ref "R4") (pin "2") (pinfunction "2_2") (pintype "passive"))
    )
    (net (code "45") (name "Net-(LCD1-VCOMH)") (class "Default")
      (node (ref "C10") (pin "1") (pinfunction "1_1") (pintype "passive"))
      (node (ref "LCD1") (pin "21") (pinfunction "VCOMH_21") (pintype "bidirectional"))
    )
    (net (code "46") (name "Net-(LED1-DI)") (class "Default")
      (node (ref "LED1") (pin "1") (pinfunction "DI_1") (pintype "input"))
      (node (ref "LED14") (pin "3") (pinfunction "DO_3") (pintype "output"))
    )
    (net (code "47") (name "Net-(LED1-DO)") (class "Default")
      (node (ref "LED1") (pin "3") (pinfunction "DO_3") (pintype "output"))
      (node (ref "LED2") (pin "1") (pinfunction "DI_1") (pintype "input"))
    )
    (net (code "48") (name "Net-(LED2-DO)") (class "Default")
      (node (ref "LED2") (pin "3") (pinfunction "DO_3") (pintype "output"))
      (node (ref "LED3") (pin "1") (pinfunction "DI_1") (pintype "input"))
    )
    (net (code "49") (name "Net-(LED3-DO)") (class "Default")
      (node (ref "LED3") (pin "3") (pinfunction "DO_3") (pintype "output"))
      (node (ref "LED4") (pin "1") (pinfunction "DI_1") (pintype "input"))
    )
    (net (code "50") (name "Net-(LED5-DO)") (class "Default")
      (node (ref "LED5") (pin "3") (pinfunction "DO_3") (pintype "output"))
      (node (ref "LED6") (pin "1") (pinfunction "DI_1") (pintype "input"))
    )
    (net (code "51") (name "Net-(LED6-DO)") (class "Default")
      (node (ref "LED6") (pin "3") (pinfunction "DO_3") (pintype "output"))
      (node (ref "LED7") (pin "1") (pinfunction "DI_1") (pintype "input"))
    )
    (net (code "52") (name "Net-(LED7-DO)") (class "Default")
      (node (ref "LED7") (pin "3") (pinfunction "DO_3") (pintype "output"))
      (node (ref "LED8") (pin "1") (pinfunction "DI_1") (pintype "input"))
    )
    (net (code "53") (name "Net-(LED8-DO)") (class "Default")
      (node (ref "LED8") (pin "3") (pinfunction "DO_3") (pintype "output"))
      (node (ref "LED9") (pin "1") (pinfunction "DI_1") (pintype "input"))
    )
    (net (code "54") (name "Net-(LED10-DI)") (class "Default")
      (node (ref "LED10") (pin "1") (pinfunction "DI_1") (pintype "input"))
      (node (ref "LED13") (pin "3") (pinfunction "DO_3") (pintype "output"))
    )
    (net (code "55") (name "Net-(LED10-DO)") (class "Default")
      (node (ref "LED10") (pin "3") (pinfunction "DO_3") (pintype "output"))
      (node (ref "LED12") (pin "1") (pinfunction "DI_1") (pintype "input"))
    )
    (net (code "56") (name "Net-(LED11-DI)") (class "Default")
      (node (ref "LED11") (pin "1") (pinfunction "DI_1") (pintype "input"))
      (node (ref "LED9") (pin "3") (pinfunction "DO_3") (pintype "output"))
    )
    (net (code "57") (name "Net-(LED11-DO)") (class "Default")
      (node (ref "LED11") (pin "3") (pinfunction "DO_3") (pintype "output"))
      (node (ref "LED13") (pin "1") (pinfunction "DI_1") (pintype "input"))
    )
    (net (code "58") (name "Net-(LED12-DO)") (class "Default")
      (node (ref "LED12") (pin "3") (pinfunction "DO_3") (pintype "output"))
      (node (ref "LED14") (pin "1") (pinfunction "DI_1") (pintype "input"))
    )
    (net (code "59") (name "Net-(S1-Pad2)") (class "Default")
      (node (ref "S1") (pin "2") (pinfunction "2_2") (pintype "bidirectional"))
      (node (ref "U$5") (pin "+") (pinfunction "+_+") (pintype "bidirectional"))
    )
    (net (code "60") (name "Net-(U$6-D+)") (class "Default")
      (node (ref "R15") (pin "2") (pinfunction "2_2") (pintype "passive"))
      (node (ref "U$6") (pin "3") (pinfunction "D+_3") (pintype "bidirectional"))
    )
    (net (code "61") (name "Net-(U$6-D-)") (class "Default")
      (node (ref "R14") (pin "2") (pinfunction "2_2") (pintype "passive"))
      (node (ref "U$6") (pin "2") (pinfunction "D-_2") (pintype "bidirectional"))
    )
    (net (code "62") (name "Net-(U$6-VCC)") (class "Default")
      (node (ref "D5") (pin "A") (pinfunction "A_A") (pintype "passive"))
      (node (ref "U$6") (pin "1") (pinfunction "VCC_1") (pintype "bidirectional"))
    )
    (net (code "63") (name "Net-(U$10-ILIM)") (class "Default")
      (node (ref "R13") (pin "1") (pinfunction "1_1") (pintype "passive"))
      (node (ref "U$10") (pin "4") (pinfunction "ILIM_4") (pintype "bidirectional"))
    )
    (net (code "64") (name "Net-(U$10-STAT)") (class "Default")
      (node (ref "R12") (pin "2") (pinfunction "2_2") (pintype "passive"))
      (node (ref "U$10") (pin "1") (pinfunction "STAT_1") (pintype "bidirectional"))
    )
    (net (code "65") (name "Net-(U$10-VSNS)") (class "Default")
      (node (ref "R11") (pin "2") (pinfunction "2_2") (pintype "passive"))
      (node (ref "U$10") (pin "3") (pinfunction "VSNS_3") (pintype "bidirectional"))
    )
    (net (code "66") (name "Net-(U$10-~{EN})") (class "Default")
      (node (ref "R2") (pin "2") (pinfunction "2_2") (pintype "passive"))
      (node (ref "U$10") (pin "2") (pinfunction "~{EN}_2") (pintype "bidirectional"))
    )
    (net (code "67") (name "Net-(U1-FB)") (class "Default")
      (node (ref "C7") (pin "2") (pinfunction "2_2") (pintype "passive"))
      (node (ref "R6") (pin "1") (pinfunction "1_1") (pintype "passive"))
      (node (ref "R7") (pin "2") (pinfunction "2_2") (pintype "passive"))
      (node (ref "U1") (pin "3") (pinfunction "FB_3") (pintype "bidirectional"))
    )
    (net (code "68") (name "Net-(U2-32K_XN(GPIO33{slash}ADC1:5{slash}TOUCH8{slash}RTC8))") (class "Default")
      (node (ref "C14") (pin "1") (pinfunction "1_1") (pintype "passive"))
      (node (ref "U2") (pin "13") (pinfunction "32K_XN(GPIO33/ADC1:5/TOUCH8/RTC8)_13") (pintype "bidirectional"))
      (node (ref "X2") (pin "P$1") (pinfunction "P$1_P$1") (pintype "bidirectional"))
    )
    (net (code "69") (name "Net-(U2-32K_XP(GPIO32{slash}ADC1:4{slash}TOUCH9{slash}RTC9))") (class "Default")
      (node (ref "C15") (pin "2") (pinfunction "2_2") (pintype "passive"))
      (node (ref "U2") (pin "12") (pinfunction "32K_XP(GPIO32/ADC1:4/TOUCH9/RTC9)_12") (pintype "bidirectional"))
      (node (ref "X2") (pin "P$2") (pinfunction "P$2_P$2") (pintype "bidirectional"))
    )
    (net (code "70") (name "Net-(U2-CAP1)") (class "Default")
      (node (ref "C19") (pin "2") (pinfunction "2_2") (pintype "passive"))
      (node (ref "C20") (pin "1") (pinfunction "1_1") (pintype "passive"))
      (node (ref "R9") (pin "2") (pinfunction "2_2") (pintype "passive"))
      (node (ref "U2") (pin "48") (pinfunction "CAP1_48") (pintype "bidirectional"))
    )
    (net (code "71") (name "Net-(U2-CAP2)") (class "Default")
      (node (ref "C19") (pin "1") (pinfunction "1_1") (pintype "passive"))
      (node (ref "R9") (pin "1") (pinfunction "1_1") (pintype "passive"))
      (node (ref "U2") (pin "47") (pinfunction "CAP2_47") (pintype "bidirectional"))
    )
    (net (code "72") (name "Net-(U2-CHIP_PU)") (class "Default")
      (node (ref "R8") (pin "2") (pinfunction "2_2") (pintype "passive"))
      (node (ref "U2") (pin "9") (pinfunction "CHIP_PU_9") (pintype "bidirectional"))
    )
    (net (code "73") (name "Net-(U2-LNA_IN)") (class "Default")
      (node (ref "C11") (pin "2") (pinfunction "2_2") (pintype "passive"))
      (node (ref "L2") (pin "1") (pinfunction "1_1") (pintype "passive"))
      (node (ref "U2") (pin "2") (pinfunction "LNA_IN_2") (pintype "bidirectional"))
    )
    (net (code "74") (name "Net-(U2-SENSOR_CAPN(GPI38{slash}ADC1:2{slash}RTC2))") (class "Default")
      (node (ref "C17") (pin "2") (pinfunction "2_2") (pintype "passive"))
      (node (ref "U2") (pin "7") (pinfunction "SENSOR_CAPN(GPI38/ADC1:2/RTC2)_7") (pintype "bidirectional"))
    )
    (net (code "75") (name "Net-(U2-SENSOR_CAPP(GPI37{slash}ADC1:1{slash}RTC1))") (class "Default")
      (node (ref "C18") (pin "1") (pinfunction "1_1") (pintype "passive"))
      (node (ref "U2") (pin "6") (pinfunction "SENSOR_CAPP(GPI37/ADC1:1/RTC1)_6") (pintype "bidirectional"))
    )
    (net (code "76") (name "Net-(U2-SENSOR_VN(GPI39{slash}ADC1:3{slash}RTC3))") (class "Default")
      (node (ref "C17") (pin "1") (pinfunction "1_1") (pintype "passive"))
      (node (ref "U2") (pin "8") (pinfunction "SENSOR_VN(GPI39/ADC1:3/RTC3)_8") (pintype "bidirectional"))
    )
    (net (code "77") (name "Net-(U2-SENSOR_VP(GPI36{slash}ADC1:0{slash}RTC0))") (class "Default")
      (node (ref "C18") (pin "2") (pinfunction "2_2") (pintype "passive"))
      (node (ref "U2") (pin "5") (pinfunction "SENSOR_VP(GPI36/ADC1:0/RTC0)_5") (pintype "bidirectional"))
    )
    (net (code "78") (name "Net-(U2-XTAL_N)") (class "Default")
      (node (ref "C13") (pin "1") (pinfunction "1_1") (pintype "passive"))
      (node (ref "U2") (pin "44") (pinfunction "XTAL_N_44") (pintype "bidirectional"))
      (node (ref "Y2") (pin "3") (pinfunction "2_3") (pintype "passive"))
    )
    (net (code "79") (name "Net-(U2-XTAL_P)") (class "Default")
      (node (ref "C16") (pin "2") (pinfunction "2_2") (pintype "passive"))
      (node (ref "U2") (pin "45") (pinfunction "XTAL_P_45") (pintype "bidirectional"))
      (node (ref "Y2") (pin "1") (pinfunction "1_1") (pintype "passive"))
    )
    (net (code "80") (name "Net-(U4-AREF)") (class "Default")
      (node (ref "C5") (pin "1") (pinfunction "1_1") (pintype "passive"))
      (node (ref "U4") (pin "42") (pinfunction "AREF_42") (pintype "bidirectional"))
    )
    (net (code "81") (name "Net-(U4-UCAP)") (class "Default")
      (node (ref "C1") (pin "1") (pinfunction "1_1") (pintype "passive"))
      (node (ref "U4") (pin "6") (pinfunction "UCAP_6") (pintype "bidirectional"))
    )
    (net (code "82") (name "Net-(U4-XTAL1)") (class "Default")
      (node (ref "C3") (pin "2") (pinfunction "2_2") (pintype "passive"))
      (node (ref "U4") (pin "17") (pinfunction "XTAL1_17") (pintype "bidirectional"))
      (node (ref "Y1") (pin "3") (pinfunction "2_3") (pintype "passive"))
    )
    (net (code "83") (name "Net-(U4-XTAL2)") (class "Default")
      (node (ref "C2") (pin "1") (pinfunction "1_1") (pintype "passive"))
      (node (ref "U4") (pin "16") (pinfunction "XTAL2_16") (pintype "bidirectional"))
      (node (ref "Y1") (pin "1") (pinfunction "1_1") (pintype "passive"))
    )
    (net (code "84") (name "Net-(U4-~{RESET})") (class "Default")
      (node (ref "R3") (pin "1") (pinfunction "1_1") (pintype "passive"))
      (node (ref "U4") (pin "13") (pinfunction "~{RESET}_13") (pintype "bidirectional"))
    )
    (net (code "85") (name "unconnected-(FTDI-CTS-Pad5)") (class "Default")
      (node (ref "FTDI") (pin "5") (pinfunction "CTS_5") (pintype "passive"))
    )
    (net (code "86") (name "unconnected-(FTDI-DTR-Pad1)") (class "Default")
      (node (ref "FTDI") (pin "1") (pinfunction "DTR_1") (pintype "passive"))
    )
    (net (code "87") (name "unconnected-(JP1-Pad1)") (class "Default")
      (node (ref "JP1") (pin "1") (pinfunction "1_1") (pintype "passive"))
    )
    (net (code "88") (name "unconnected-(JP1-Pad2)") (class "Default")
      (node (ref "JP1") (pin "2") (pinfunction "2_2") (pintype "passive"))
    )
    (net (code "89") (name "unconnected-(JP1-Pad3)") (class "Default")
      (node (ref "JP1") (pin "3") (pinfunction "3_3") (pintype "passive"))
    )
    (net (code "90") (name "unconnected-(JP1-Pad4)") (class "Default")
      (node (ref "JP1") (pin "4") (pinfunction "4_4") (pintype "passive"))
    )
    (net (code "91") (name "unconnected-(LCD1-BS2-Pad6)") (class "Default")
      (node (ref "LCD1") (pin "6") (pinfunction "BS2_6") (pintype "bidirectional"))
    )
    (net (code "92") (name "unconnected-(LCD1-D2-Pad15)") (class "Default")
      (node (ref "LCD1") (pin "15") (pinfunction "D2_15") (pintype "bidirectional"))
    )
    (net (code "93") (name "unconnected-(LCD1-D3-Pad16)") (class "Default")
      (node (ref "LCD1") (pin "16") (pinfunction "D3_16") (pintype "bidirectional"))
    )
    (net (code "94") (name "unconnected-(LCD1-D4-Pad17)") (class "Default")
      (node (ref "LCD1") (pin "17") (pinfunction "D4_17") (pintype "bidirectional"))
    )
    (net (code "95") (name "unconnected-(LCD1-D5-Pad18)") (class "Default")
      (node (ref "LCD1") (pin "18") (pinfunction "D5_18") (pintype "bidirectional"))
    )
    (net (code "96") (name "unconnected-(LCD1-D6-Pad19)") (class "Default")
      (node (ref "LCD1") (pin "19") (pinfunction "D6_19") (pintype "bidirectional"))
    )
    (net (code "97") (name "unconnected-(LCD1-D7-Pad20)") (class "Default")
      (node (ref "LCD1") (pin "20") (pinfunction "D7_20") (pintype "bidirectional"))
    )
    (net (code "98") (name "unconnected-(LCD1-E-Pad12)") (class "Default")
      (node (ref "LCD1") (pin "12") (pinfunction "E_12") (pintype "bidirectional"))
    )
    (net (code "99") (name "unconnected-(LCD1-NC1-Pad1)") (class "Default")
      (node (ref "LCD1") (pin "1") (pinfunction "NC1_1") (pintype "no_connect"))
    )
    (net (code "100") (name "unconnected-(LCD1-NC2-Pad23)") (class "Default")
      (node (ref "LCD1") (pin "23") (pinfunction "NC2_23") (pintype "no_connect"))
    )
    (net (code "101") (name "unconnected-(LCD1-R{slash}W#-Pad11)") (class "Default")
      (node (ref "LCD1") (pin "11") (pinfunction "R/W#_11") (pintype "bidirectional"))
    )
    (net (code "102") (name "unconnected-(LED4-DO-Pad3)") (class "Default")
      (node (ref "LED4") (pin "3") (pinfunction "DO_3") (pintype "output"))
    )
    (net (code "103") (name "unconnected-(S1-Pad3)") (class "Default")
      (node (ref "S1") (pin "3") (pinfunction "3_3") (pintype "bidirectional"))
    )
    (net (code "104") (name "unconnected-(S1-Pad6)") (class "Default")
      (node (ref "S1") (pin "6") (pinfunction "6_6") (pintype "bidirectional"))
    )
    (net (code "105") (name "unconnected-(U$6-ID-Pad4)") (class "Default")
      (node (ref "U$6") (pin "4") (pinfunction "ID_4") (pintype "bidirectional"))
    )
    (net (code "106") (name "unconnected-(U2-VDD3P3_SDIO-Pad26)") (class "Default")
      (node (ref "U2") (pin "26") (pinfunction "VDD3P3_SDIO_26") (pintype "bidirectional"))
    )
    (net (code "107") (name "unconnected-(U2-VDET_1(GPI34{slash}ADC1:6)-Pad10)") (class "Default")
      (node (ref "U2") (pin "10") (pinfunction "VDET_1(GPI34/ADC1:6)_10") (pintype "bidirectional"))
    )
    (net (code "108") (name "unconnected-(U2-VDET_2(GPI35{slash}ADC1:7)-Pad11)") (class "Default")
      (node (ref "U2") (pin "11") (pinfunction "VDET_2(GPI35/ADC1:7)_11") (pintype "bidirectional"))
    )
    (net (code "109") (name "unconnected-(U4-PB0(SS)-Pad11)") (class "Default")
      (node (ref "U4") (pin "11") (pinfunction "PB0(SS)_11") (pintype "bidirectional"))
    )
    (net (code "110") (name "unconnected-(U4-PB1(SCK)-Pad9)") (class "Default")
      (node (ref "U4") (pin "9") (pinfunction "PB1(SCK)_9") (pintype "bidirectional"))
    )
    (net (code "111") (name "unconnected-(U4-PB2(MOSI)-Pad10)") (class "Default")
      (node (ref "U4") (pin "10") (pinfunction "PB2(MOSI)_10") (pintype "bidirectional"))
    )
    (net (code "112") (name "unconnected-(U4-PB3(MISO)-Pad8)") (class "Default")
      (node (ref "U4") (pin "8") (pinfunction "PB3(MISO)_8") (pintype "bidirectional"))
    )
    (net (code "113") (name "unconnected-(U4-PB4(ADC11)-Pad28)") (class "Default")
      (node (ref "U4") (pin "28") (pinfunction "PB4(ADC11)_28") (pintype "bidirectional"))
    )
    (net (code "114") (name "unconnected-(U4-PB5(ADC12)-Pad29)") (class "Default")
      (node (ref "U4") (pin "29") (pinfunction "PB5(ADC12)_29") (pintype "bidirectional"))
    )
    (net (code "115") (name "unconnected-(U4-PB6(ADC13)-Pad30)") (class "Default")
      (node (ref "U4") (pin "30") (pinfunction "PB6(ADC13)_30") (pintype "bidirectional"))
    )
    (net (code "116") (name "unconnected-(U4-PB7-Pad12)") (class "Default")
      (node (ref "U4") (pin "12") (pinfunction "PB7_12") (pintype "bidirectional"))
    )
    (net (code "117") (name "unconnected-(U4-PC6-Pad31)") (class "Default")
      (node (ref "U4") (pin "31") (pinfunction "PC6_31") (pintype "bidirectional"))
    )
    (net (code "118") (name "unconnected-(U4-PC7-Pad32)") (class "Default")
      (node (ref "U4") (pin "32") (pinfunction "PC7_32") (pintype "bidirectional"))
    )
    (net (code "119") (name "unconnected-(U4-PD0(SCL)-Pad18)") (class "Default")
      (node (ref "U4") (pin "18") (pinfunction "PD0(SCL)_18") (pintype "bidirectional"))
    )
    (net (code "120") (name "unconnected-(U4-PD1(SDA)-Pad19)") (class "Default")
      (node (ref "U4") (pin "19") (pinfunction "PD1(SDA)_19") (pintype "bidirectional"))
    )
    (net (code "121") (name "unconnected-(U4-PD4(ADC8)-Pad25)") (class "Default")
      (node (ref "U4") (pin "25") (pinfunction "PD4(ADC8)_25") (pintype "bidirectional"))
    )
    (net (code "122") (name "unconnected-(U4-PD5-Pad22)") (class "Default")
      (node (ref "U4") (pin "22") (pinfunction "PD5_22") (pintype "bidirectional"))
    )
    (net (code "123") (name "unconnected-(U4-PD6(ADC9)-Pad26)") (class "Default")
      (node (ref "U4") (pin "26") (pinfunction "PD6(ADC9)_26") (pintype "bidirectional"))
    )
    (net (code "124") (name "unconnected-(U4-PD7(ADC10)-Pad27)") (class "Default")
      (node (ref "U4") (pin "27") (pinfunction "PD7(ADC10)_27") (pintype "bidirectional"))
    )
    (net (code "125") (name "unconnected-(U4-PF0(ADC0)-Pad41)") (class "Default")
      (node (ref "U4") (pin "41") (pinfunction "PF0(ADC0)_41") (pintype "bidirectional"))
    )
    (net (code "126") (name "unconnected-(U4-PF1(ADC1)-Pad40)") (class "Default")
      (node (ref "U4") (pin "40") (pinfunction "PF1(ADC1)_40") (pintype "bidirectional"))
    )
    (net (code "127") (name "unconnected-(U4-PF4(ADC4)-Pad39)") (class "Default")
      (node (ref "U4") (pin "39") (pinfunction "PF4(ADC4)_39") (pintype "bidirectional"))
    )
    (net (code "128") (name "unconnected-(U4-PF5(ADC5)-Pad38)") (class "Default")
      (node (ref "U4") (pin "38") (pinfunction "PF5(ADC5)_38") (pintype "bidirectional"))
    )
    (net (code "129") (name "unconnected-(U4-PF6(ADC6)-Pad37)") (class "Default")
      (node (ref "U4") (pin "37") (pinfunction "PF6(ADC6)_37") (pintype "bidirectional"))
    )
    (net (code "130") (name "unconnected-(U4-PF7(ADC7)-Pad36)") (class "Default")
      (node (ref "U4") (pin "36") (pinfunction "PF7(ADC7)_36") (pintype "bidirectional"))
    )
  )
)
